# AnalogCapture.net
KiCad netlist of a schematic drawn in Altium Designer
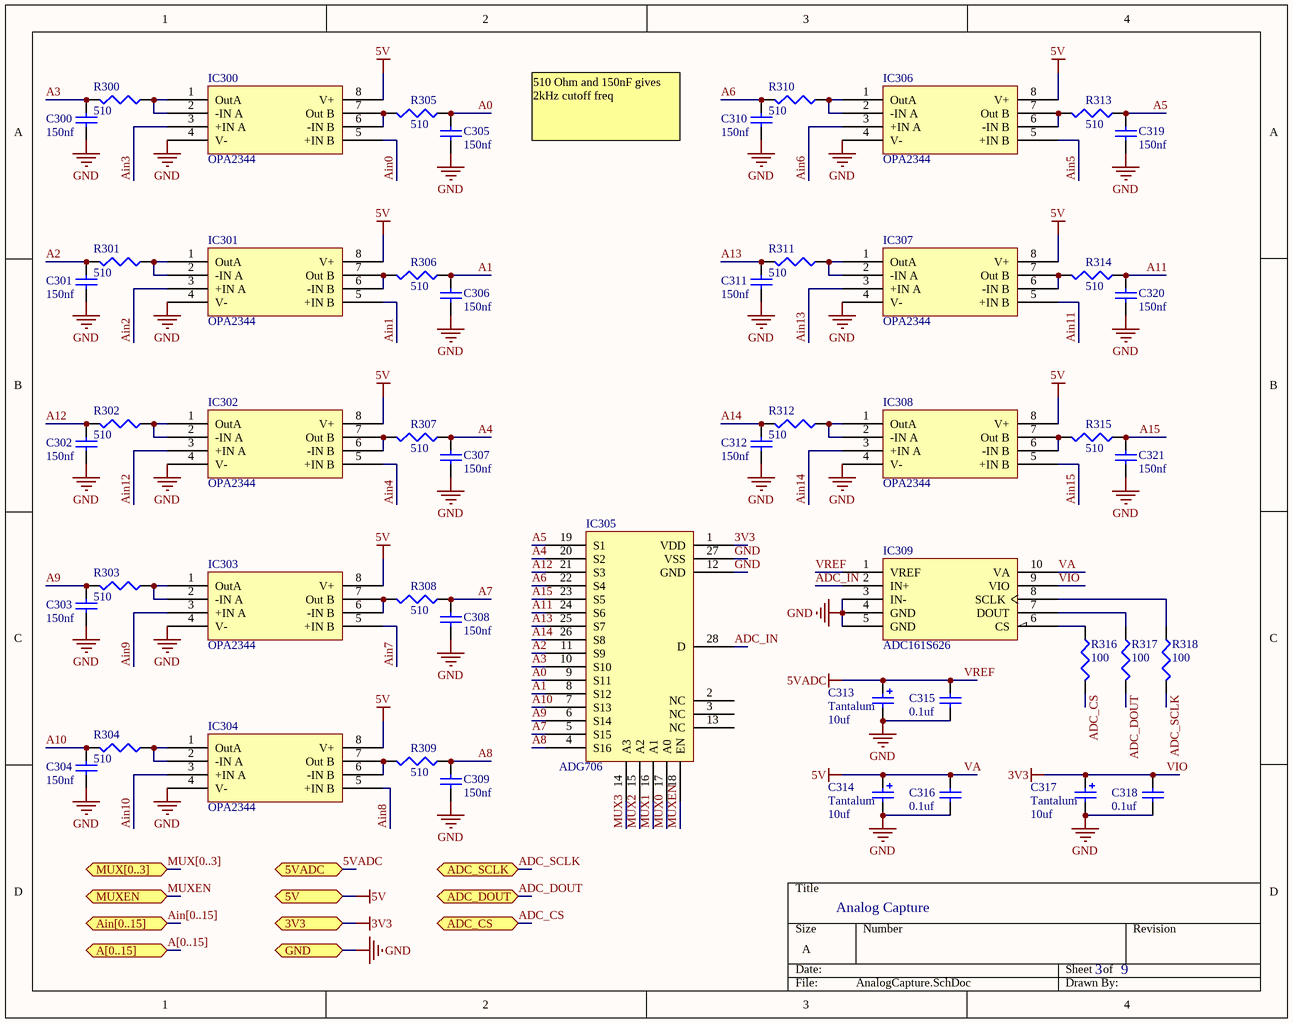
[diagram p0: AnalogCapture.SchDoc]

(export (version "E")
  (design (tool "Eeschema 10.0.6"))
  (components
    (comp (ref "C300")
      (value "150nf")
      (footprint "SMD0603")
      (description "Ceramic Chip Capacitor")
      (fields (field (name "Comment") "Cap"))
      (libsource (lib "Components") (part "Capacitor Ceramic"))
    )
    (comp (ref "C301")
      (value "150nf")
      (footprint "SMD0603")
      (description "Ceramic Chip Capacitor")
      (fields (field (name "Comment") "Cap"))
      (libsource (lib "Components") (part "Capacitor Ceramic"))
    )
    (comp (ref "C302")
      (value "150nf")
      (footprint "SMD0603")
      (description "Ceramic Chip Capacitor")
      (fields (field (name "Comment") "Cap"))
      (libsource (lib "Components") (part "Capacitor Ceramic"))
    )
    (comp (ref "C303")
      (value "150nf")
      (footprint "SMD0603")
      (description "Ceramic Chip Capacitor")
      (fields (field (name "Comment") "Cap"))
      (libsource (lib "Components") (part "Capacitor Ceramic"))
    )
    (comp (ref "C304")
      (value "150nf")
      (footprint "SMD0603")
      (description "Ceramic Chip Capacitor")
      (fields (field (name "Comment") "Cap"))
      (libsource (lib "Components") (part "Capacitor Ceramic"))
    )
    (comp (ref "C305")
      (value "150nf")
      (footprint "SMD0603")
      (description "Ceramic Chip Capacitor")
      (fields (field (name "Comment") "Cap"))
      (libsource (lib "Components") (part "Capacitor Ceramic"))
    )
    (comp (ref "C306")
      (value "150nf")
      (footprint "SMD0603")
      (description "Ceramic Chip Capacitor")
      (fields (field (name "Comment") "Cap"))
      (libsource (lib "Components") (part "Capacitor Ceramic"))
    )
    (comp (ref "C307")
      (value "150nf")
      (footprint "SMD0603")
      (description "Ceramic Chip Capacitor")
      (fields (field (name "Comment") "Cap"))
      (libsource (lib "Components") (part "Capacitor Ceramic"))
    )
    (comp (ref "C308")
      (value "150nf")
      (footprint "SMD0603")
      (description "Ceramic Chip Capacitor")
      (fields (field (name "Comment") "Cap"))
      (libsource (lib "Components") (part "Capacitor Ceramic"))
    )
    (comp (ref "C309")
      (value "150nf")
      (footprint "SMD0603")
      (description "Ceramic Chip Capacitor")
      (fields (field (name "Comment") "Cap"))
      (libsource (lib "Components") (part "Capacitor Ceramic"))
    )
    (comp (ref "C310")
      (value "150nf")
      (footprint "SMD0603")
      (description "Ceramic Chip Capacitor")
      (fields (field (name "Comment") "Cap"))
      (libsource (lib "Components") (part "Capacitor Ceramic"))
    )
    (comp (ref "C311")
      (value "150nf")
      (footprint "SMD0603")
      (description "Ceramic Chip Capacitor")
      (fields (field (name "Comment") "Cap"))
      (libsource (lib "Components") (part "Capacitor Ceramic"))
    )
    (comp (ref "C312")
      (value "150nf")
      (footprint "SMD0603")
      (description "Ceramic Chip Capacitor")
      (fields (field (name "Comment") "Cap"))
      (libsource (lib "Components") (part "Capacitor Ceramic"))
    )
    (comp (ref "C313")
      (value "Tantalum")
      (footprint "SMD1206 Polarized")
      (description "Polarized Capacitor (Surface Mount)")
      (fields (field (name "ALTIUM_VALUE") "10uf"))
      (libsource (lib "Components") (part "Capacitor Polarized"))
    )
    (comp (ref "C314")
      (value "Tantalum")
      (footprint "SMD1206 Polarized")
      (description "Polarized Capacitor (Surface Mount)")
      (fields (field (name "ALTIUM_VALUE") "10uf"))
      (libsource (lib "Components") (part "Capacitor Polarized"))
    )
    (comp (ref "C315")
      (value "0.1uf")
      (footprint "SMD0603")
      (description "Ceramic Chip Capacitor")
      (fields (field (name "Comment") "Capacitor Ceramic"))
      (libsource (lib "Components") (part "Capacitor Ceramic"))
    )
    (comp (ref "C316")
      (value "0.1uf")
      (footprint "SMD0603")
      (description "Ceramic Chip Capacitor")
      (fields (field (name "Comment") "Capacitor Ceramic"))
      (libsource (lib "Components") (part "Capacitor Ceramic"))
    )
    (comp (ref "C317")
      (value "Tantalum")
      (footprint "SMD1206 Polarized")
      (description "Polarized Capacitor (Surface Mount)")
      (fields (field (name "ALTIUM_VALUE") "10uf"))
      (libsource (lib "Components") (part "Capacitor Polarized"))
    )
    (comp (ref "C318")
      (value "0.1uf")
      (footprint "SMD0603")
      (description "Ceramic Chip Capacitor")
      (fields (field (name "Comment") "Capacitor Ceramic"))
      (libsource (lib "Components") (part "Capacitor Ceramic"))
    )
    (comp (ref "C319")
      (value "150nf")
      (footprint "SMD0603")
      (description "Ceramic Chip Capacitor")
      (fields (field (name "Comment") "Cap"))
      (libsource (lib "Components") (part "Capacitor Ceramic"))
    )
    (comp (ref "C320")
      (value "150nf")
      (footprint "SMD0603")
      (description "Ceramic Chip Capacitor")
      (fields (field (name "Comment") "Cap"))
      (libsource (lib "Components") (part "Capacitor Ceramic"))
    )
    (comp (ref "C321")
      (value "150nf")
      (footprint "SMD0603")
      (description "Ceramic Chip Capacitor")
      (fields (field (name "Comment") "Cap"))
      (libsource (lib "Components") (part "Capacitor Ceramic"))
    )
    (comp (ref "IC300")
      (value "OPA2344")
      (footprint "SOIC-8")
      (description "Rail to rail opamp")
      (libsource (lib "Components") (part "OPA2344"))
    )
    (comp (ref "IC301")
      (value "OPA2344")
      (footprint "SOIC-8")
      (description "Rail to rail opamp")
      (libsource (lib "Components") (part "OPA2344"))
    )
    (comp (ref "IC302")
      (value "OPA2344")
      (footprint "SOIC-8")
      (description "Rail to rail opamp")
      (libsource (lib "Components") (part "OPA2344"))
    )
    (comp (ref "IC303")
      (value "OPA2344")
      (footprint "SOIC-8")
      (description "Rail to rail opamp")
      (libsource (lib "Components") (part "OPA2344"))
    )
    (comp (ref "IC304")
      (value "OPA2344")
      (footprint "SOIC-8")
      (description "Rail to rail opamp")
      (libsource (lib "Components") (part "OPA2344"))
    )
    (comp (ref "IC305")
      (value "ADG706")
      (footprint "TSSOP-28")
      (description "16:1 Mux")
      (libsource (lib "Components") (part "ADG706"))
    )
    (comp (ref "IC306")
      (value "OPA2344")
      (footprint "SOIC-8")
      (description "Rail to rail opamp")
      (libsource (lib "Components") (part "OPA2344"))
    )
    (comp (ref "IC307")
      (value "OPA2344")
      (footprint "SOIC-8")
      (description "Rail to rail opamp")
      (libsource (lib "Components") (part "OPA2344"))
    )
    (comp (ref "IC308")
      (value "OPA2344")
      (footprint "SOIC-8")
      (description "Rail to rail opamp")
      (libsource (lib "Components") (part "OPA2344"))
    )
    (comp (ref "IC309")
      (value "ADC161S626")
      (footprint "VSSOP-10 (DGS)")
      (description "TI ADC; 250ksps")
      (libsource (lib "Components") (part "ADC161S626"))
    )
    (comp (ref "R300")
      (value "510")
      (footprint "SMD0603")
      (description "Resistor")
      (fields (field (name "Comment") "Res"))
      (libsource (lib "Components") (part "Resistor"))
    )
    (comp (ref "R301")
      (value "510")
      (footprint "SMD0603")
      (description "Resistor")
      (fields (field (name "Comment") "Res"))
      (libsource (lib "Components") (part "Resistor"))
    )
    (comp (ref "R302")
      (value "510")
      (footprint "SMD0603")
      (description "Resistor")
      (fields (field (name "Comment") "Res"))
      (libsource (lib "Components") (part "Resistor"))
    )
    (comp (ref "R303")
      (value "510")
      (footprint "SMD0603")
      (description "Resistor")
      (fields (field (name "Comment") "Res"))
      (libsource (lib "Components") (part "Resistor"))
    )
    (comp (ref "R304")
      (value "510")
      (footprint "SMD0603")
      (description "Resistor")
      (fields (field (name "Comment") "Res"))
      (libsource (lib "Components") (part "Resistor"))
    )
    (comp (ref "R305")
      (value "510")
      (footprint "SMD0603")
      (description "Resistor")
      (fields (field (name "Comment") "Res"))
      (libsource (lib "Components") (part "Resistor"))
    )
    (comp (ref "R306")
      (value "510")
      (footprint "SMD0603")
      (description "Resistor")
      (fields (field (name "Comment") "Res"))
      (libsource (lib "Components") (part "Resistor"))
    )
    (comp (ref "R307")
      (value "510")
      (footprint "SMD0603")
      (description "Resistor")
      (fields (field (name "Comment") "Res"))
      (libsource (lib "Components") (part "Resistor"))
    )
    (comp (ref "R308")
      (value "510")
      (footprint "SMD0603")
      (description "Resistor")
      (fields (field (name "Comment") "Res"))
      (libsource (lib "Components") (part "Resistor"))
    )
    (comp (ref "R309")
      (value "510")
      (footprint "SMD0603")
      (description "Resistor")
      (fields (field (name "Comment") "Res"))
      (libsource (lib "Components") (part "Resistor"))
    )
    (comp (ref "R310")
      (value "510")
      (footprint "SMD0603")
      (description "Resistor")
      (fields (field (name "Comment") "Res"))
      (libsource (lib "Components") (part "Resistor"))
    )
    (comp (ref "R311")
      (value "510")
      (footprint "SMD0603")
      (description "Resistor")
      (fields (field (name "Comment") "Res"))
      (libsource (lib "Components") (part "Resistor"))
    )
    (comp (ref "R312")
      (value "510")
      (footprint "SMD0603")
      (description "Resistor")
      (fields (field (name "Comment") "Res"))
      (libsource (lib "Components") (part "Resistor"))
    )
    (comp (ref "R313")
      (value "510")
      (footprint "SMD0603")
      (description "Resistor")
      (fields (field (name "Comment") "Res"))
      (libsource (lib "Components") (part "Resistor"))
    )
    (comp (ref "R314")
      (value "510")
      (footprint "SMD0603")
      (description "Resistor")
      (fields (field (name "Comment") "Res"))
      (libsource (lib "Components") (part "Resistor"))
    )
    (comp (ref "R315")
      (value "510")
      (footprint "SMD0603")
      (description "Resistor")
      (fields (field (name "Comment") "Res"))
      (libsource (lib "Components") (part "Resistor"))
    )
    (comp (ref "R316")
      (value "100")
      (footprint "SMD0603")
      (description "Resistor")
      (fields (field (name "Comment") "Res"))
      (libsource (lib "Components") (part "Resistor"))
    )
    (comp (ref "R317")
      (value "100")
      (footprint "SMD0603")
      (description "Resistor")
      (fields (field (name "Comment") "Res"))
      (libsource (lib "Components") (part "Resistor"))
    )
    (comp (ref "R318")
      (value "100")
      (footprint "SMD0603")
      (description "Resistor")
      (fields (field (name "Comment") "Res"))
      (libsource (lib "Components") (part "Resistor"))
    )
  )
  (nets
    (net (code "1") (name "/A0") (class "Default")
      (node (ref "C305") (pin "2") (pinfunction "2_2") (pintype "passive"))
      (node (ref "IC305") (pin "9") (pinfunction "S11_9") (pintype "passive"))
      (node (ref "R305") (pin "1") (pinfunction "1_1") (pintype "passive"))
    )
    (net (code "2") (name "/A1") (class "Default")
      (node (ref "C306") (pin "2") (pinfunction "2_2") (pintype "passive"))
      (node (ref "IC305") (pin "8") (pinfunction "S12_8") (pintype "passive"))
      (node (ref "R306") (pin "1") (pinfunction "1_1") (pintype "passive"))
    )
    (net (code "3") (name "/A2") (class "Default")
      (node (ref "C301") (pin "1") (pinfunction "1_1") (pintype "passive"))
      (node (ref "IC305") (pin "11") (pinfunction "S9_11") (pintype "passive"))
      (node (ref "R301") (pin "2") (pinfunction "2_2") (pintype "passive"))
    )
    (net (code "4") (name "/A3") (class "Default")
      (node (ref "C300") (pin "1") (pinfunction "1_1") (pintype "passive"))
      (node (ref "IC305") (pin "10") (pinfunction "S10_10") (pintype "passive"))
      (node (ref "R300") (pin "2") (pinfunction "2_2") (pintype "passive"))
    )
    (net (code "5") (name "/A4") (class "Default")
      (node (ref "C307") (pin "2") (pinfunction "2_2") (pintype "passive"))
      (node (ref "IC305") (pin "20") (pinfunction "S2_20") (pintype "passive"))
      (node (ref "R307") (pin "1") (pinfunction "1_1") (pintype "passive"))
    )
    (net (code "6") (name "/A5") (class "Default")
      (node (ref "C319") (pin "2") (pinfunction "2_2") (pintype "passive"))
      (node (ref "IC305") (pin "19") (pinfunction "S1_19") (pintype "passive"))
      (node (ref "R313") (pin "1") (pinfunction "1_1") (pintype "passive"))
    )
    (net (code "7") (name "/A6") (class "Default")
      (node (ref "C310") (pin "1") (pinfunction "1_1") (pintype "passive"))
      (node (ref "IC305") (pin "22") (pinfunction "S4_22") (pintype "passive"))
      (node (ref "R310") (pin "2") (pinfunction "2_2") (pintype "passive"))
    )
    (net (code "8") (name "/A7") (class "Default")
      (node (ref "C308") (pin "2") (pinfunction "2_2") (pintype "passive"))
      (node (ref "IC305") (pin "5") (pinfunction "S15_5") (pintype "passive"))
      (node (ref "R308") (pin "1") (pinfunction "1_1") (pintype "passive"))
    )
    (net (code "9") (name "/A8") (class "Default")
      (node (ref "C309") (pin "2") (pinfunction "2_2") (pintype "passive"))
      (node (ref "IC305") (pin "4") (pinfunction "S16_4") (pintype "passive"))
      (node (ref "R309") (pin "1") (pinfunction "1_1") (pintype "passive"))
    )
    (net (code "10") (name "/A9") (class "Default")
      (node (ref "C303") (pin "1") (pinfunction "1_1") (pintype "passive"))
      (node (ref "IC305") (pin "6") (pinfunction "S14_6") (pintype "passive"))
      (node (ref "R303") (pin "2") (pinfunction "2_2") (pintype "passive"))
    )
    (net (code "11") (name "/A10") (class "Default")
      (node (ref "C304") (pin "1") (pinfunction "1_1") (pintype "passive"))
      (node (ref "IC305") (pin "7") (pinfunction "S13_7") (pintype "passive"))
      (node (ref "R304") (pin "2") (pinfunction "2_2") (pintype "passive"))
    )
    (net (code "12") (name "/A11") (class "Default")
      (node (ref "C320") (pin "2") (pinfunction "2_2") (pintype "passive"))
      (node (ref "IC305") (pin "24") (pinfunction "S6_24") (pintype "passive"))
      (node (ref "R314") (pin "1") (pinfunction "1_1") (pintype "passive"))
    )
    (net (code "13") (name "/A12") (class "Default")
      (node (ref "C302") (pin "1") (pinfunction "1_1") (pintype "passive"))
      (node (ref "IC305") (pin "21") (pinfunction "S3_21") (pintype "passive"))
      (node (ref "R302") (pin "2") (pinfunction "2_2") (pintype "passive"))
    )
    (net (code "14") (name "/A13") (class "Default")
      (node (ref "C311") (pin "1") (pinfunction "1_1") (pintype "passive"))
      (node (ref "IC305") (pin "25") (pinfunction "S7_25") (pintype "passive"))
      (node (ref "R311") (pin "2") (pinfunction "2_2") (pintype "passive"))
    )
    (net (code "15") (name "/A14") (class "Default")
      (node (ref "C312") (pin "1") (pinfunction "1_1") (pintype "passive"))
      (node (ref "IC305") (pin "26") (pinfunction "S8_26") (pintype "passive"))
      (node (ref "R312") (pin "2") (pinfunction "2_2") (pintype "passive"))
    )
    (net (code "16") (name "/A15") (class "Default")
      (node (ref "C321") (pin "2") (pinfunction "2_2") (pintype "passive"))
      (node (ref "IC305") (pin "23") (pinfunction "S5_23") (pintype "passive"))
      (node (ref "R315") (pin "1") (pinfunction "1_1") (pintype "passive"))
    )
    (net (code "17") (name "/ADC_CS") (class "Default")
      (node (ref "R316") (pin "2") (pinfunction "2_2") (pintype "passive"))
    )
    (net (code "18") (name "/ADC_DOUT") (class "Default")
      (node (ref "R317") (pin "2") (pinfunction "2_2") (pintype "passive"))
    )
    (net (code "19") (name "/ADC_IN") (class "Default")
      (node (ref "IC305") (pin "28") (pinfunction "D_28") (pintype "passive"))
      (node (ref "IC309") (pin "2") (pinfunction "IN+_2") (pintype "passive"))
    )
    (net (code "20") (name "/ADC_SCLK") (class "Default")
      (node (ref "R318") (pin "2") (pinfunction "2_2") (pintype "passive"))
    )
    (net (code "22") (name "/Ain0") (class "Default")
      (node (ref "IC300") (pin "5") (pinfunction "+IN_B_5") (pintype "passive"))
    )
    (net (code "23") (name "/Ain1") (class "Default")
      (node (ref "IC301") (pin "5") (pinfunction "+IN_B_5") (pintype "passive"))
    )
    (net (code "24") (name "/Ain2") (class "Default")
      (node (ref "IC301") (pin "3") (pinfunction "+IN_A_3") (pintype "passive"))
    )
    (net (code "25") (name "/Ain3") (class "Default")
      (node (ref "IC300") (pin "3") (pinfunction "+IN_A_3") (pintype "passive"))
    )
    (net (code "26") (name "/Ain4") (class "Default")
      (node (ref "IC302") (pin "5") (pinfunction "+IN_B_5") (pintype "passive"))
    )
    (net (code "27") (name "/Ain5") (class "Default")
      (node (ref "IC306") (pin "5") (pinfunction "+IN_B_5") (pintype "passive"))
    )
    (net (code "28") (name "/Ain6") (class "Default")
      (node (ref "IC306") (pin "3") (pinfunction "+IN_A_3") (pintype "passive"))
    )
    (net (code "29") (name "/Ain7") (class "Default")
      (node (ref "IC303") (pin "5") (pinfunction "+IN_B_5") (pintype "passive"))
    )
    (net (code "30") (name "/Ain8") (class "Default")
      (node (ref "IC304") (pin "5") (pinfunction "+IN_B_5") (pintype "passive"))
    )
    (net (code "31") (name "/Ain9") (class "Default")
      (node (ref "IC303") (pin "3") (pinfunction "+IN_A_3") (pintype "passive"))
    )
    (net (code "32") (name "/Ain10") (class "Default")
      (node (ref "IC304") (pin "3") (pinfunction "+IN_A_3") (pintype "passive"))
    )
    (net (code "33") (name "/Ain11") (class "Default")
      (node (ref "IC307") (pin "5") (pinfunction "+IN_B_5") (pintype "passive"))
    )
    (net (code "34") (name "/Ain12") (class "Default")
      (node (ref "IC302") (pin "3") (pinfunction "+IN_A_3") (pintype "passive"))
    )
    (net (code "35") (name "/Ain13") (class "Default")
      (node (ref "IC307") (pin "3") (pinfunction "+IN_A_3") (pintype "passive"))
    )
    (net (code "36") (name "/Ain14") (class "Default")
      (node (ref "IC308") (pin "3") (pinfunction "+IN_A_3") (pintype "passive"))
    )
    (net (code "37") (name "/Ain15") (class "Default")
      (node (ref "IC308") (pin "5") (pinfunction "+IN_B_5") (pintype "passive"))
    )
    (net (code "39") (name "/MUX0") (class "Default")
      (node (ref "IC305") (pin "17") (pinfunction "A0_17") (pintype "passive"))
    )
    (net (code "40") (name "/MUX1") (class "Default")
      (node (ref "IC305") (pin "16") (pinfunction "A1_16") (pintype "passive"))
    )
    (net (code "41") (name "/MUX2") (class "Default")
      (node (ref "IC305") (pin "15") (pinfunction "A2_15") (pintype "passive"))
    )
    (net (code "42") (name "/MUX3") (class "Default")
      (node (ref "IC305") (pin "14") (pinfunction "A3_14") (pintype "passive"))
    )
    (net (code "43") (name "/MUXEN") (class "Default")
      (node (ref "IC305") (pin "18") (pinfunction "EN_18") (pintype "passive"))
    )
    (net (code "45") (name "3V3") (class "Default")
      (node (ref "C317") (pin "1") (pinfunction "1_1") (pintype "passive"))
      (node (ref "C318") (pin "2") (pinfunction "2_2") (pintype "passive"))
      (node (ref "IC305") (pin "1") (pinfunction "VDD_1") (pintype "passive"))
      (node (ref "IC309") (pin "9") (pinfunction "VIO_9") (pintype "passive"))
    )
    (net (code "46") (name "5V") (class "Default")
      (node (ref "C314") (pin "1") (pinfunction "1_1") (pintype "passive"))
      (node (ref "C316") (pin "2") (pinfunction "2_2") (pintype "passive"))
      (node (ref "IC300") (pin "8") (pinfunction "V+_8") (pintype "passive"))
      (node (ref "IC301") (pin "8") (pinfunction "V+_8") (pintype "passive"))
      (node (ref "IC302") (pin "8") (pinfunction "V+_8") (pintype "passive"))
      (node (ref "IC303") (pin "8") (pinfunction "V+_8") (pintype "passive"))
      (node (ref "IC304") (pin "8") (pinfunction "V+_8") (pintype "passive"))
      (node (ref "IC306") (pin "8") (pinfunction "V+_8") (pintype "passive"))
      (node (ref "IC307") (pin "8") (pinfunction "V+_8") (pintype "passive"))
      (node (ref "IC308") (pin "8") (pinfunction "V+_8") (pintype "passive"))
      (node (ref "IC309") (pin "10") (pinfunction "VA_10") (pintype "passive"))
    )
    (net (code "47") (name "5VADC") (class "Default")
      (node (ref "C313") (pin "1") (pinfunction "1_1") (pintype "passive"))
      (node (ref "C315") (pin "2") (pinfunction "2_2") (pintype "passive"))
      (node (ref "IC309") (pin "1") (pinfunction "VREF_1") (pintype "passive"))
    )
    (net (code "48") (name "GND") (class "Default")
      (node (ref "C300") (pin "2") (pinfunction "2_2") (pintype "passive"))
      (node (ref "C301") (pin "2") (pinfunction "2_2") (pintype "passive"))
      (node (ref "C302") (pin "2") (pinfunction "2_2") (pintype "passive"))
      (node (ref "C303") (pin "2") (pinfunction "2_2") (pintype "passive"))
      (node (ref "C304") (pin "2") (pinfunction "2_2") (pintype "passive"))
      (node (ref "C305") (pin "1") (pinfunction "1_1") (pintype "passive"))
      (node (ref "C306") (pin "1") (pinfunction "1_1") (pintype "passive"))
      (node (ref "C307") (pin "1") (pinfunction "1_1") (pintype "passive"))
      (node (ref "C308") (pin "1") (pinfunction "1_1") (pintype "passive"))
      (node (ref "C309") (pin "1") (pinfunction "1_1") (pintype "passive"))
      (node (ref "C310") (pin "2") (pinfunction "2_2") (pintype "passive"))
      (node (ref "C311") (pin "2") (pinfunction "2_2") (pintype "passive"))
      (node (ref "C312") (pin "2") (pinfunction "2_2") (pintype "passive"))
      (node (ref "C313") (pin "2") (pinfunction "2_2") (pintype "passive"))
      (node (ref "C314") (pin "2") (pinfunction "2_2") (pintype "passive"))
      (node (ref "C315") (pin "1") (pinfunction "1_1") (pintype "passive"))
      (node (ref "C316") (pin "1") (pinfunction "1_1") (pintype "passive"))
      (node (ref "C317") (pin "2") (pinfunction "2_2") (pintype "passive"))
      (node (ref "C318") (pin "1") (pinfunction "1_1") (pintype "passive"))
      (node (ref "C319") (pin "1") (pinfunction "1_1") (pintype "passive"))
      (node (ref "C320") (pin "1") (pinfunction "1_1") (pintype "passive"))
      (node (ref "C321") (pin "1") (pinfunction "1_1") (pintype "passive"))
      (node (ref "IC300") (pin "4") (pinfunction "V-_4") (pintype "passive"))
      (node (ref "IC301") (pin "4") (pinfunction "V-_4") (pintype "passive"))
      (node (ref "IC302") (pin "4") (pinfunction "V-_4") (pintype "passive"))
      (node (ref "IC303") (pin "4") (pinfunction "V-_4") (pintype "passive"))
      (node (ref "IC304") (pin "4") (pinfunction "V-_4") (pintype "passive"))
      (node (ref "IC305") (pin "12") (pinfunction "GND_12") (pintype "passive"))
      (node (ref "IC305") (pin "27") (pinfunction "VSS_27") (pintype "passive"))
      (node (ref "IC306") (pin "4") (pinfunction "V-_4") (pintype "passive"))
      (node (ref "IC307") (pin "4") (pinfunction "V-_4") (pintype "passive"))
      (node (ref "IC308") (pin "4") (pinfunction "V-_4") (pintype "passive"))
      (node (ref "IC309") (pin "3") (pinfunction "IN-_3") (pintype "passive"))
      (node (ref "IC309") (pin "4") (pinfunction "GND_4") (pintype "passive"))
      (node (ref "IC309") (pin "5") (pinfunction "GND_5") (pintype "passive"))
    )
    (net (code "49") (name "Net-(IC300--IN_A)") (class "Default")
      (node (ref "IC300") (pin "1") (pinfunction "OutA_1") (pintype "passive"))
      (node (ref "IC300") (pin "2") (pinfunction "-IN_A_2") (pintype "passive"))
      (node (ref "R300") (pin "1") (pinfunction "1_1") (pintype "passive"))
    )
    (net (code "50") (name "Net-(IC300--IN_B)") (class "Default")
      (node (ref "IC300") (pin "6") (pinfunction "-IN_B_6") (pintype "passive"))
      (node (ref "IC300") (pin "7") (pinfunction "Out_B_7") (pintype "passive"))
      (node (ref "R305") (pin "2") (pinfunction "2_2") (pintype "passive"))
    )
    (net (code "51") (name "Net-(IC301--IN_A)") (class "Default")
      (node (ref "IC301") (pin "1") (pinfunction "OutA_1") (pintype "passive"))
      (node (ref "IC301") (pin "2") (pinfunction "-IN_A_2") (pintype "passive"))
      (node (ref "R301") (pin "1") (pinfunction "1_1") (pintype "passive"))
    )
    (net (code "52") (name "Net-(IC301--IN_B)") (class "Default")
      (node (ref "IC301") (pin "6") (pinfunction "-IN_B_6") (pintype "passive"))
      (node (ref "IC301") (pin "7") (pinfunction "Out_B_7") (pintype "passive"))
      (node (ref "R306") (pin "2") (pinfunction "2_2") (pintype "passive"))
    )
    (net (code "53") (name "Net-(IC302--IN_A)") (class "Default")
      (node (ref "IC302") (pin "1") (pinfunction "OutA_1") (pintype "passive"))
      (node (ref "IC302") (pin "2") (pinfunction "-IN_A_2") (pintype "passive"))
      (node (ref "R302") (pin "1") (pinfunction "1_1") (pintype "passive"))
    )
    (net (code "54") (name "Net-(IC302--IN_B)") (class "Default")
      (node (ref "IC302") (pin "6") (pinfunction "-IN_B_6") (pintype "passive"))
      (node (ref "IC302") (pin "7") (pinfunction "Out_B_7") (pintype "passive"))
      (node (ref "R307") (pin "2") (pinfunction "2_2") (pintype "passive"))
    )
    (net (code "55") (name "Net-(IC303--IN_A)") (class "Default")
      (node (ref "IC303") (pin "1") (pinfunction "OutA_1") (pintype "passive"))
      (node (ref "IC303") (pin "2") (pinfunction "-IN_A_2") (pintype "passive"))
      (node (ref "R303") (pin "1") (pinfunction "1_1") (pintype "passive"))
    )
    (net (code "56") (name "Net-(IC303--IN_B)") (class "Default")
      (node (ref "IC303") (pin "6") (pinfunction "-IN_B_6") (pintype "passive"))
      (node (ref "IC303") (pin "7") (pinfunction "Out_B_7") (pintype "passive"))
      (node (ref "R308") (pin "2") (pinfunction "2_2") (pintype "passive"))
    )
    (net (code "57") (name "Net-(IC304--IN_A)") (class "Default")
      (node (ref "IC304") (pin "1") (pinfunction "OutA_1") (pintype "passive"))
      (node (ref "IC304") (pin "2") (pinfunction "-IN_A_2") (pintype "passive"))
      (node (ref "R304") (pin "1") (pinfunction "1_1") (pintype "passive"))
    )
    (net (code "58") (name "Net-(IC304--IN_B)") (class "Default")
      (node (ref "IC304") (pin "6") (pinfunction "-IN_B_6") (pintype "passive"))
      (node (ref "IC304") (pin "7") (pinfunction "Out_B_7") (pintype "passive"))
      (node (ref "R309") (pin "2") (pinfunction "2_2") (pintype "passive"))
    )
    (net (code "59") (name "Net-(IC306--IN_A)") (class "Default")
      (node (ref "IC306") (pin "1") (pinfunction "OutA_1") (pintype "passive"))
      (node (ref "IC306") (pin "2") (pinfunction "-IN_A_2") (pintype "passive"))
      (node (ref "R310") (pin "1") (pinfunction "1_1") (pintype "passive"))
    )
    (net (code "60") (name "Net-(IC306--IN_B)") (class "Default")
      (node (ref "IC306") (pin "6") (pinfunction "-IN_B_6") (pintype "passive"))
      (node (ref "IC306") (pin "7") (pinfunction "Out_B_7") (pintype "passive"))
      (node (ref "R313") (pin "2") (pinfunction "2_2") (pintype "passive"))
    )
    (net (code "61") (name "Net-(IC307--IN_A)") (class "Default")
      (node (ref "IC307") (pin "1") (pinfunction "OutA_1") (pintype "passive"))
      (node (ref "IC307") (pin "2") (pinfunction "-IN_A_2") (pintype "passive"))
      (node (ref "R311") (pin "1") (pinfunction "1_1") (pintype "passive"))
    )
    (net (code "62") (name "Net-(IC307--IN_B)") (class "Default")
      (node (ref "IC307") (pin "6") (pinfunction "-IN_B_6") (pintype "passive"))
      (node (ref "IC307") (pin "7") (pinfunction "Out_B_7") (pintype "passive"))
      (node (ref "R314") (pin "2") (pinfunction "2_2") (pintype "passive"))
    )
    (net (code "63") (name "Net-(IC308--IN_A)") (class "Default")
      (node (ref "IC308") (pin "1") (pinfunction "OutA_1") (pintype "passive"))
      (node (ref "IC308") (pin "2") (pinfunction "-IN_A_2") (pintype "passive"))
      (node (ref "R312") (pin "1") (pinfunction "1_1") (pintype "passive"))
    )
    (net (code "64") (name "Net-(IC308--IN_B)") (class "Default")
      (node (ref "IC308") (pin "6") (pinfunction "-IN_B_6") (pintype "passive"))
      (node (ref "IC308") (pin "7") (pinfunction "Out_B_7") (pintype "passive"))
      (node (ref "R315") (pin "2") (pinfunction "2_2") (pintype "passive"))
    )
    (net (code "65") (name "Net-(IC309-CS)") (class "Default")
      (node (ref "IC309") (pin "6") (pinfunction "CS_6") (pintype "passive"))
      (node (ref "R316") (pin "1") (pinfunction "1_1") (pintype "passive"))
    )
    (net (code "66") (name "Net-(IC309-DOUT)") (class "Default")
      (node (ref "IC309") (pin "7") (pinfunction "DOUT_7") (pintype "passive"))
      (node (ref "R317") (pin "1") (pinfunction "1_1") (pintype "passive"))
    )
    (net (code "67") (name "Net-(IC309-SCLK)") (class "Default")
      (node (ref "IC309") (pin "8") (pinfunction "SCLK_8") (pintype "passive"))
      (node (ref "R318") (pin "1") (pinfunction "1_1") (pintype "passive"))
    )
    (net (code "68") (name "unconnected-(IC305-NC-Pad2)") (class "Default")
      (node (ref "IC305") (pin "2") (pinfunction "NC_2") (pintype "passive"))
    )
    (net (code "69") (name "unconnected-(IC305-NC-Pad3)") (class "Default")
      (node (ref "IC305") (pin "3") (pinfunction "NC_3") (pintype "passive"))
    )
    (net (code "70") (name "unconnected-(IC305-NC-Pad13)") (class "Default")
      (node (ref "IC305") (pin "13") (pinfunction "NC_13") (pintype "passive"))
    )
  )
)
